# source_eagle.net
KiCad netlist of a schematic drawn in EAGLE
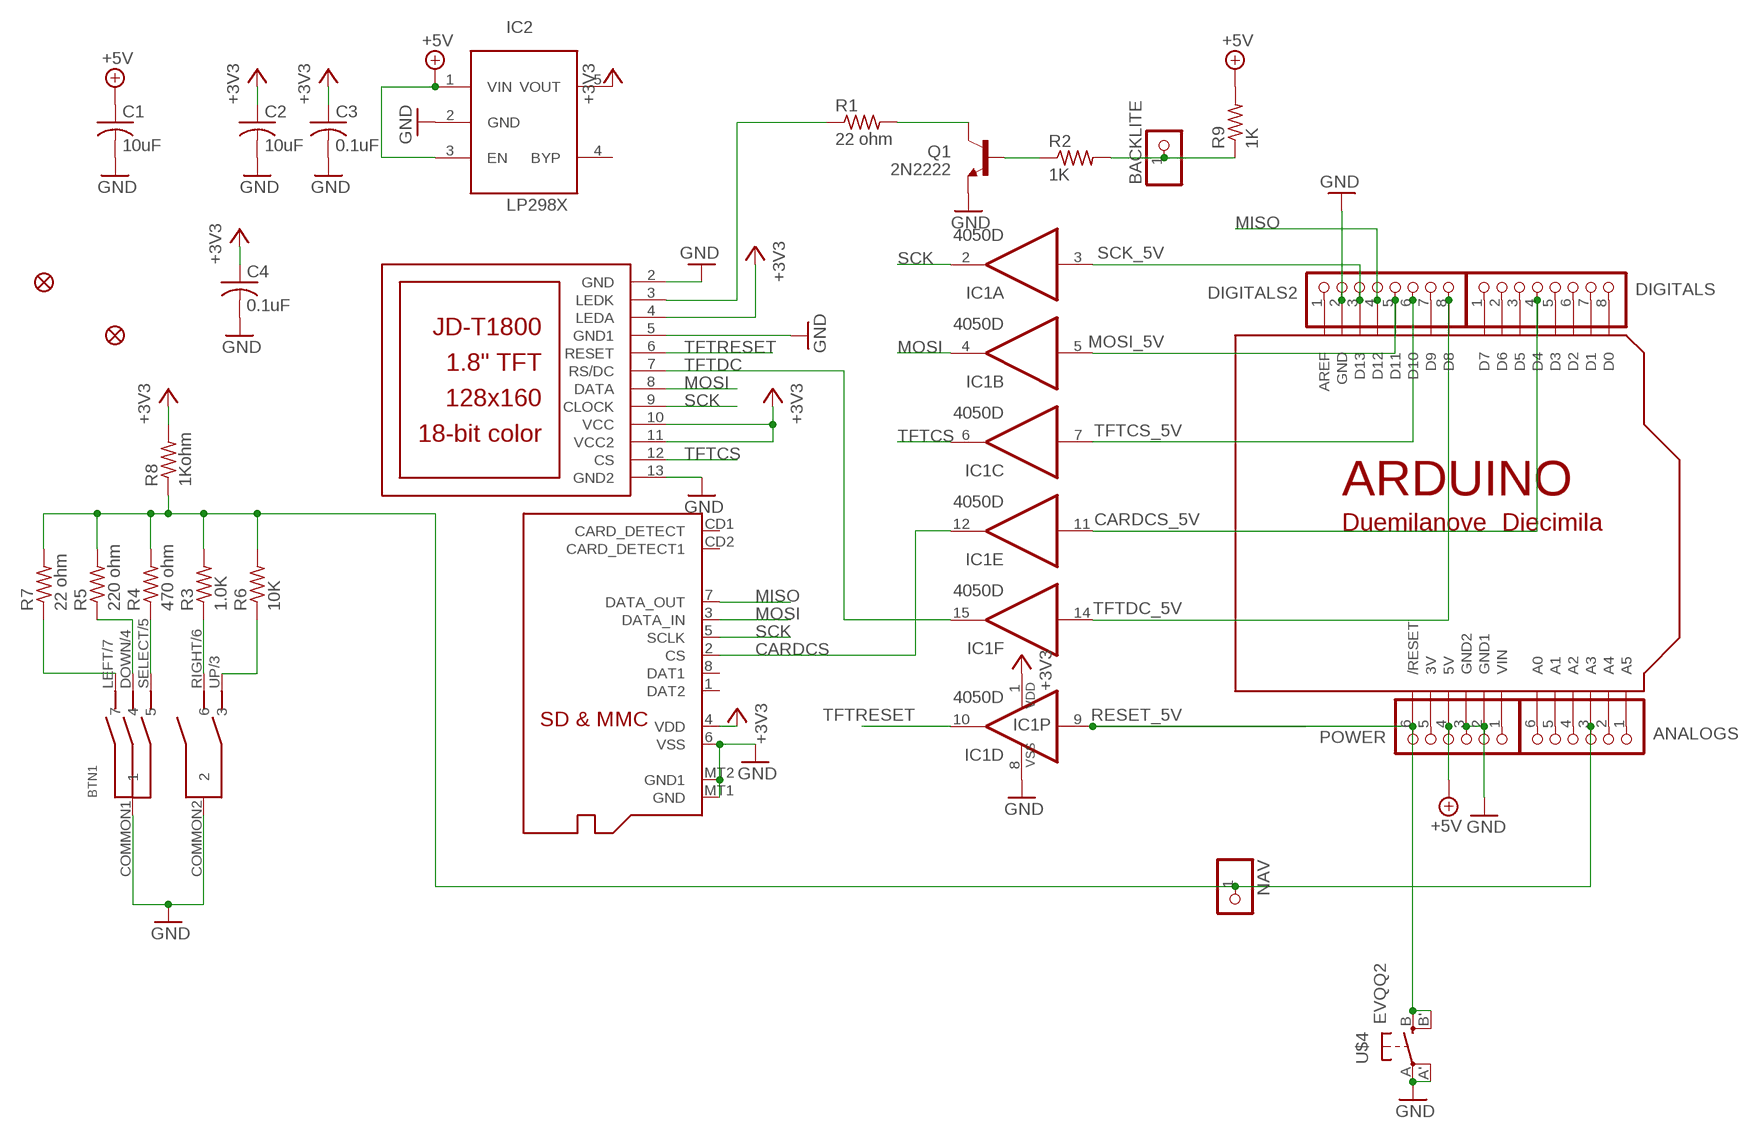
[diagram p0: schematic, sheet 1]

(export (version "E")
  (design (tool "Eeschema 10.0.6"))
  (components
    (comp (ref "ANALOGS")
      (value "PINHD-1X6CB")
      (footprint "eagle-import:1X06-CLEANBIG")
      (libsource (lib "eagle-import") (part "PINHD-1X6CB"))
    )
    (comp (ref "BACKLITE")
      (value "PINHD-1X1")
      (footprint "eagle-import:1X01")
      (libsource (lib "eagle-import") (part "PINHD-1X1"))
    )
    (comp (ref "BTN1")
      (value "SWITCH_4WAY_TPA511GLFS")
      (footprint "eagle-import:SWITCH_4WAY_TPA511GLFS")
      (libsource (lib "eagle-import") (part "SWITCH_4WAY_TPA511GLFS"))
    )
    (comp (ref "C1")
      (value "10uF")
      (footprint "eagle-import:C0805K")
      (libsource (lib "eagle-import") (part "C-USC0805K"))
    )
    (comp (ref "C2")
      (value "10uF")
      (footprint "eagle-import:C0805K")
      (libsource (lib "eagle-import") (part "C-USC0805K"))
    )
    (comp (ref "C3")
      (value "0.1uF")
      (footprint "eagle-import:C0805K")
      (libsource (lib "eagle-import") (part "C-USC0805K"))
    )
    (comp (ref "C4")
      (value "0.1uF")
      (footprint "eagle-import:C0805K")
      (libsource (lib "eagle-import") (part "C-USC0805K"))
    )
    (comp (ref "DIGITALS")
      (value "PINHD-1X8CLEANBIG")
      (footprint "eagle-import:1X08-CLEANBIG")
      (libsource (lib "eagle-import") (part "PINHD-1X8CLEANBIG"))
    )
    (comp (ref "DIGITALS2")
      (value "PINHD-1X8CLEANBIG")
      (footprint "eagle-import:1X08-CLEANBIG")
      (libsource (lib "eagle-import") (part "PINHD-1X8CLEANBIG"))
    )
    (comp (ref "FID1")
      (value "FIDUCIAL1X2.5")
      (footprint "eagle-import:FIDUCIAL-1X2.5")
      (libsource (lib "eagle-import") (part "FIDUCIAL1X2.5"))
    )
    (comp (ref "FID3")
      (value "FIDUCIAL1X2.5")
      (footprint "eagle-import:FIDUCIAL-1X2.5")
      (libsource (lib "eagle-import") (part "FIDUCIAL1X2.5"))
    )
    (comp (ref "IC1")
      (value "4050D")
      (footprint "eagle-import:SO16")
      (libsource (lib "eagle-import") (part "4050D"))
    )
    (comp (ref "IC2")
      (value "RT9193-33GB")
      (footprint "eagle-import:SOT23-5L")
      (libsource (lib "eagle-import") (part "LP298XS"))
    )
    (comp (ref "NAV")
      (value "PINHD-1X1")
      (footprint "eagle-import:1X01")
      (libsource (lib "eagle-import") (part "PINHD-1X1"))
    )
    (comp (ref "POWER")
      (value "PINHD-1X6CB")
      (footprint "eagle-import:1X06-CLEANBIG")
      (libsource (lib "eagle-import") (part "PINHD-1X6CB"))
    )
    (comp (ref "Q1")
      (value "2N2222")
      (footprint "eagle-import:SOT23-BEC")
      (libsource (lib "eagle-import") (part "-NPN-SOT23-BECMMBT2222ALT1"))
    )
    (comp (ref "R1")
      (value "22 ohm")
      (footprint "eagle-import:R0805")
      (libsource (lib "eagle-import") (part "R-US_R0805"))
    )
    (comp (ref "R2")
      (value "1K")
      (footprint "eagle-import:R0805")
      (libsource (lib "eagle-import") (part "R-US_R0805"))
    )
    (comp (ref "R3")
      (value "1.0K")
      (footprint "eagle-import:R0805")
      (libsource (lib "eagle-import") (part "R-US_R0805"))
    )
    (comp (ref "R4")
      (value "470 ohm")
      (footprint "eagle-import:R0805")
      (libsource (lib "eagle-import") (part "R-US_R0805"))
    )
    (comp (ref "R5")
      (value "220 ohm")
      (footprint "eagle-import:R0805")
      (libsource (lib "eagle-import") (part "R-US_R0805"))
    )
    (comp (ref "R6")
      (value "10K")
      (footprint "eagle-import:R0805")
      (libsource (lib "eagle-import") (part "R-US_R0805"))
    )
    (comp (ref "R7")
      (value "22 ohm")
      (footprint "eagle-import:R0805")
      (libsource (lib "eagle-import") (part "R-US_R0805"))
    )
    (comp (ref "R8")
      (value "1Kohm")
      (footprint "eagle-import:R0805")
      (libsource (lib "eagle-import") (part "R-US_R0805"))
    )
    (comp (ref "R9")
      (value "1K")
      (footprint "eagle-import:R0805")
      (libsource (lib "eagle-import") (part "R-US_R0805"))
    )
    (comp (ref "U$1")
      (value "JD-T1800")
      (footprint "eagle-import:JD-T1800")
      (libsource (lib "eagle-import") (part "JD-T1800"))
    )
    (comp (ref "U$2")
      (value "ARDUINOUNO")
      (footprint "eagle-import:ARDUINO")
      (libsource (lib "eagle-import") (part "ARDUINOUNO"))
    )
    (comp (ref "U$3")
      (value "MICROSD")
      (footprint "eagle-import:MICROSD")
      (libsource (lib "eagle-import") (part "MICROSD"))
    )
    (comp (ref "U$4")
      (value "EVQQ2")
      (footprint "eagle-import:EVQ-Q2")
      (libsource (lib "eagle-import") (part "EVQQ2"))
    )
  )
  (nets
    (net (code "1") (name "+3V3") (class "Default")
      (node (ref "C2") (pin "1") (pinfunction "1_1") (pintype "passive"))
      (node (ref "C3") (pin "1") (pinfunction "1_1") (pintype "passive"))
      (node (ref "C4") (pin "1") (pinfunction "1_1") (pintype "passive"))
      (node (ref "IC1") (pin "1") (pinfunction "VDD_1") (pintype "power_in"))
      (node (ref "IC2") (pin "5") (pinfunction "VOUT_5") (pintype "bidirectional"))
      (node (ref "R8") (pin "2") (pinfunction "2_2") (pintype "passive"))
      (node (ref "U$1") (pin "10") (pinfunction "VCC_10") (pintype "power_in"))
      (node (ref "U$1") (pin "11") (pinfunction "VCC2_11") (pintype "power_in"))
      (node (ref "U$1") (pin "4") (pinfunction "LEDA_4") (pintype "input"))
      (node (ref "U$3") (pin "4") (pinfunction "VDD_4") (pintype "power_in"))
    )
    (net (code "2") (name "+5V") (class "Default")
      (node (ref "C1") (pin "1") (pinfunction "1_1") (pintype "passive"))
      (node (ref "IC2") (pin "1") (pinfunction "VIN_1") (pintype "bidirectional"))
      (node (ref "IC2") (pin "3") (pinfunction "EN_3") (pintype "bidirectional"))
      (node (ref "POWER") (pin "4") (pinfunction "4_4") (pintype "passive"))
      (node (ref "R9") (pin "2") (pinfunction "2_2") (pintype "passive"))
      (node (ref "U$2") (pin "5V") (pinfunction "5V_5V") (pintype "power_in"))
    )
    (net (code "3") (name "/CARDCS") (class "Default")
      (node (ref "IC1") (pin "12") (pinfunction "O_12") (pintype "output"))
      (node (ref "U$3") (pin "2") (pinfunction "CS_2") (pintype "input"))
    )
    (net (code "4") (name "/CARDCS_5V") (class "Default")
      (node (ref "DIGITALS") (pin "4") (pinfunction "4_4") (pintype "passive"))
      (node (ref "IC1") (pin "11") (pinfunction "I_11") (pintype "input"))
      (node (ref "U$2") (pin "D4") (pinfunction "D4_D4") (pintype "bidirectional"))
    )
    (net (code "5") (name "/MISO") (class "Default")
      (node (ref "DIGITALS2") (pin "4") (pinfunction "4_4") (pintype "passive"))
      (node (ref "U$2") (pin "D12") (pinfunction "D12_D12") (pintype "bidirectional"))
      (node (ref "U$3") (pin "7") (pinfunction "DATA_OUT_7") (pintype "output"))
    )
    (net (code "6") (name "/MOSI") (class "Default")
      (node (ref "IC1") (pin "4") (pinfunction "O_4") (pintype "output"))
      (node (ref "U$1") (pin "8") (pinfunction "DATA_8") (pintype "bidirectional"))
      (node (ref "U$3") (pin "3") (pinfunction "DATA_IN_3") (pintype "input"))
    )
    (net (code "7") (name "/MOSI_5V") (class "Default")
      (node (ref "DIGITALS2") (pin "5") (pinfunction "5_5") (pintype "passive"))
      (node (ref "IC1") (pin "5") (pinfunction "I_5") (pintype "input"))
      (node (ref "U$2") (pin "D11") (pinfunction "D11_D11") (pintype "bidirectional"))
    )
    (net (code "8") (name "/RESET_5V") (class "Default")
      (node (ref "IC1") (pin "9") (pinfunction "I_9") (pintype "input"))
      (node (ref "POWER") (pin "6") (pinfunction "6_6") (pintype "passive"))
      (node (ref "U$2") (pin "RESET") (pinfunction "/RESET_RESET") (pintype "bidirectional"))
      (node (ref "U$4") (pin "B") (pinfunction "S_B") (pintype "passive"))
      (node (ref "U$4") (pin "B'") (pinfunction "S1_B'") (pintype "passive"))
    )
    (net (code "9") (name "/SCK") (class "Default")
      (node (ref "IC1") (pin "2") (pinfunction "O_2") (pintype "output"))
      (node (ref "U$1") (pin "9") (pinfunction "CLOCK_9") (pintype "input"))
      (node (ref "U$3") (pin "5") (pinfunction "SCLK_5") (pintype "input"))
    )
    (net (code "10") (name "/SCK_5V") (class "Default")
      (node (ref "DIGITALS2") (pin "3") (pinfunction "3_3") (pintype "passive"))
      (node (ref "IC1") (pin "3") (pinfunction "I_3") (pintype "input"))
      (node (ref "U$2") (pin "D13") (pinfunction "D13_D13") (pintype "bidirectional"))
    )
    (net (code "11") (name "/TFTCS") (class "Default")
      (node (ref "IC1") (pin "6") (pinfunction "O_6") (pintype "output"))
      (node (ref "U$1") (pin "12") (pinfunction "CS_12") (pintype "input"))
    )
    (net (code "12") (name "/TFTCS_5V") (class "Default")
      (node (ref "DIGITALS2") (pin "6") (pinfunction "6_6") (pintype "passive"))
      (node (ref "IC1") (pin "7") (pinfunction "I_7") (pintype "input"))
      (node (ref "U$2") (pin "D10") (pinfunction "D10_D10") (pintype "bidirectional"))
    )
    (net (code "13") (name "/TFTDC") (class "Default")
      (node (ref "IC1") (pin "15") (pinfunction "O_15") (pintype "output"))
      (node (ref "U$1") (pin "7") (pinfunction "RS/DC_7") (pintype "input"))
    )
    (net (code "14") (name "/TFTDC_5V") (class "Default")
      (node (ref "DIGITALS2") (pin "8") (pinfunction "8_8") (pintype "passive"))
      (node (ref "IC1") (pin "14") (pinfunction "I_14") (pintype "input"))
      (node (ref "U$2") (pin "D8") (pinfunction "D8_D8") (pintype "bidirectional"))
    )
    (net (code "15") (name "/TFTRESET") (class "Default")
      (node (ref "IC1") (pin "10") (pinfunction "O_10") (pintype "output"))
      (node (ref "U$1") (pin "6") (pinfunction "RESET_6") (pintype "input"))
    )
    (net (code "16") (name "GND") (class "Default")
      (node (ref "BTN1") (pin "COMMON1") (pinfunction "1_COMMON1") (pintype "bidirectional"))
      (node (ref "BTN1") (pin "COMMON2") (pinfunction "2_COMMON2") (pintype "bidirectional"))
      (node (ref "C1") (pin "2") (pinfunction "2_2") (pintype "passive"))
      (node (ref "C2") (pin "2") (pinfunction "2_2") (pintype "passive"))
      (node (ref "C3") (pin "2") (pinfunction "2_2") (pintype "passive"))
      (node (ref "C4") (pin "2") (pinfunction "2_2") (pintype "passive"))
      (node (ref "DIGITALS2") (pin "2") (pinfunction "2_2") (pintype "passive"))
      (node (ref "IC1") (pin "8") (pinfunction "VSS_8") (pintype "power_in"))
      (node (ref "IC2") (pin "2") (pinfunction "GND_2") (pintype "bidirectional"))
      (node (ref "POWER") (pin "2") (pinfunction "2_2") (pintype "passive"))
      (node (ref "POWER") (pin "3") (pinfunction "3_3") (pintype "passive"))
      (node (ref "Q1") (pin "E") (pinfunction "E_E") (pintype "passive"))
      (node (ref "U$1") (pin "13") (pinfunction "GND2_13") (pintype "power_in"))
      (node (ref "U$1") (pin "2") (pinfunction "GND_2") (pintype "power_in"))
      (node (ref "U$1") (pin "5") (pinfunction "GND1_5") (pintype "power_in"))
      (node (ref "U$2") (pin "GND") (pinfunction "GND_GND") (pintype "power_in"))
      (node (ref "U$2") (pin "GND1") (pinfunction "GND1_GND1") (pintype "power_in"))
      (node (ref "U$2") (pin "GND2") (pinfunction "GND2_GND2") (pintype "power_in"))
      (node (ref "U$3") (pin "6") (pinfunction "VSS_6") (pintype "power_in"))
      (node (ref "U$3") (pin "MT1") (pinfunction "GND_MT1") (pintype "power_in"))
      (node (ref "U$3") (pin "MT2") (pinfunction "GND1_MT2") (pintype "power_in"))
      (node (ref "U$4") (pin "A") (pinfunction "P_A") (pintype "passive"))
      (node (ref "U$4") (pin "A'") (pinfunction "P1_A'") (pintype "passive"))
    )
    (net (code "17") (name "Net-(ANALOGS-Pad1)") (class "Default")
      (node (ref "ANALOGS") (pin "1") (pinfunction "1_1") (pintype "passive"))
      (node (ref "U$2") (pin "A5") (pinfunction "A5_A5") (pintype "bidirectional"))
    )
    (net (code "18") (name "Net-(ANALOGS-Pad2)") (class "Default")
      (node (ref "ANALOGS") (pin "2") (pinfunction "2_2") (pintype "passive"))
      (node (ref "U$2") (pin "A4") (pinfunction "A4_A4") (pintype "bidirectional"))
    )
    (net (code "19") (name "Net-(ANALOGS-Pad3)") (class "Default")
      (node (ref "ANALOGS") (pin "3") (pinfunction "3_3") (pintype "passive"))
      (node (ref "NAV") (pin "1") (pinfunction "1_1") (pintype "passive"))
      (node (ref "R3") (pin "2") (pinfunction "2_2") (pintype "passive"))
      (node (ref "R4") (pin "2") (pinfunction "2_2") (pintype "passive"))
      (node (ref "R5") (pin "2") (pinfunction "2_2") (pintype "passive"))
      (node (ref "R6") (pin "2") (pinfunction "2_2") (pintype "passive"))
      (node (ref "R7") (pin "2") (pinfunction "2_2") (pintype "passive"))
      (node (ref "R8") (pin "1") (pinfunction "1_1") (pintype "passive"))
      (node (ref "U$2") (pin "A3") (pinfunction "A3_A3") (pintype "bidirectional"))
    )
    (net (code "20") (name "Net-(ANALOGS-Pad4)") (class "Default")
      (node (ref "ANALOGS") (pin "4") (pinfunction "4_4") (pintype "passive"))
      (node (ref "U$2") (pin "A2") (pinfunction "A2_A2") (pintype "bidirectional"))
    )
    (net (code "21") (name "Net-(ANALOGS-Pad5)") (class "Default")
      (node (ref "ANALOGS") (pin "5") (pinfunction "5_5") (pintype "passive"))
      (node (ref "U$2") (pin "A1") (pinfunction "A1_A1") (pintype "bidirectional"))
    )
    (net (code "22") (name "Net-(ANALOGS-Pad6)") (class "Default")
      (node (ref "ANALOGS") (pin "6") (pinfunction "6_6") (pintype "passive"))
      (node (ref "U$2") (pin "A0") (pinfunction "A0_A0") (pintype "bidirectional"))
    )
    (net (code "23") (name "Net-(BACKLITE-Pad1)") (class "Default")
      (node (ref "BACKLITE") (pin "1") (pinfunction "1_1") (pintype "passive"))
      (node (ref "R2") (pin "2") (pinfunction "2_2") (pintype "passive"))
      (node (ref "R9") (pin "1") (pinfunction "1_1") (pintype "passive"))
    )
    (net (code "24") (name "Net-(BTN1-3)") (class "Default")
      (node (ref "BTN1") (pin "UP/3") (pinfunction "3_UP/3") (pintype "bidirectional"))
      (node (ref "R6") (pin "1") (pinfunction "1_1") (pintype "passive"))
    )
    (net (code "25") (name "Net-(BTN1-4)") (class "Default")
      (node (ref "BTN1") (pin "DOWN/4") (pinfunction "4_DOWN/4") (pintype "bidirectional"))
      (node (ref "R5") (pin "1") (pinfunction "1_1") (pintype "passive"))
    )
    (net (code "26") (name "Net-(BTN1-5)") (class "Default")
      (node (ref "BTN1") (pin "SELECT/5") (pinfunction "5_SELECT/5") (pintype "bidirectional"))
      (node (ref "R4") (pin "1") (pinfunction "1_1") (pintype "passive"))
    )
    (net (code "27") (name "Net-(BTN1-6)") (class "Default")
      (node (ref "BTN1") (pin "RIGHT/6") (pinfunction "6_RIGHT/6") (pintype "bidirectional"))
      (node (ref "R3") (pin "1") (pinfunction "1_1") (pintype "passive"))
    )
    (net (code "28") (name "Net-(BTN1-7)") (class "Default")
      (node (ref "BTN1") (pin "LEFT/7") (pinfunction "7_LEFT/7") (pintype "bidirectional"))
      (node (ref "R7") (pin "1") (pinfunction "1_1") (pintype "passive"))
    )
    (net (code "29") (name "Net-(DIGITALS-Pad1)") (class "Default")
      (node (ref "DIGITALS") (pin "1") (pinfunction "1_1") (pintype "passive"))
      (node (ref "U$2") (pin "D7") (pinfunction "D7_D7") (pintype "bidirectional"))
    )
    (net (code "30") (name "Net-(DIGITALS-Pad2)") (class "Default")
      (node (ref "DIGITALS") (pin "2") (pinfunction "2_2") (pintype "passive"))
      (node (ref "U$2") (pin "D6") (pinfunction "D6_D6") (pintype "bidirectional"))
    )
    (net (code "31") (name "Net-(DIGITALS-Pad3)") (class "Default")
      (node (ref "DIGITALS") (pin "3") (pinfunction "3_3") (pintype "passive"))
      (node (ref "U$2") (pin "D5") (pinfunction "D5_D5") (pintype "bidirectional"))
    )
    (net (code "32") (name "Net-(DIGITALS-Pad5)") (class "Default")
      (node (ref "DIGITALS") (pin "5") (pinfunction "5_5") (pintype "passive"))
      (node (ref "U$2") (pin "D3") (pinfunction "D3_D3") (pintype "bidirectional"))
    )
    (net (code "33") (name "Net-(DIGITALS-Pad6)") (class "Default")
      (node (ref "DIGITALS") (pin "6") (pinfunction "6_6") (pintype "passive"))
      (node (ref "U$2") (pin "D2") (pinfunction "D2_D2") (pintype "bidirectional"))
    )
    (net (code "34") (name "Net-(DIGITALS-Pad7)") (class "Default")
      (node (ref "DIGITALS") (pin "7") (pinfunction "7_7") (pintype "passive"))
      (node (ref "U$2") (pin "D1") (pinfunction "D1_D1") (pintype "bidirectional"))
    )
    (net (code "35") (name "Net-(DIGITALS-Pad8)") (class "Default")
      (node (ref "DIGITALS") (pin "8") (pinfunction "8_8") (pintype "passive"))
      (node (ref "U$2") (pin "D0") (pinfunction "D0_D0") (pintype "bidirectional"))
    )
    (net (code "36") (name "Net-(DIGITALS2-Pad1)") (class "Default")
      (node (ref "DIGITALS2") (pin "1") (pinfunction "1_1") (pintype "passive"))
      (node (ref "U$2") (pin "AREF") (pinfunction "AREF_AREF") (pintype "bidirectional"))
    )
    (net (code "37") (name "Net-(DIGITALS2-Pad7)") (class "Default")
      (node (ref "DIGITALS2") (pin "7") (pinfunction "7_7") (pintype "passive"))
      (node (ref "U$2") (pin "D9") (pinfunction "D9_D9") (pintype "bidirectional"))
    )
    (net (code "38") (name "Net-(POWER-Pad1)") (class "Default")
      (node (ref "POWER") (pin "1") (pinfunction "1_1") (pintype "passive"))
      (node (ref "U$2") (pin "VIN") (pinfunction "VIN_VIN") (pintype "power_in"))
    )
    (net (code "39") (name "Net-(POWER-Pad5)") (class "Default")
      (node (ref "POWER") (pin "5") (pinfunction "5_5") (pintype "passive"))
      (node (ref "U$2") (pin "3V") (pinfunction "3V_3V") (pintype "power_in"))
    )
    (net (code "40") (name "Net-(Q1-PadB)") (class "Default")
      (node (ref "Q1") (pin "B") (pinfunction "B_B") (pintype "passive"))
      (node (ref "R2") (pin "1") (pinfunction "1_1") (pintype "passive"))
    )
    (net (code "41") (name "Net-(Q1-PadC)") (class "Default")
      (node (ref "Q1") (pin "C") (pinfunction "C_C") (pintype "passive"))
      (node (ref "R1") (pin "2") (pinfunction "2_2") (pintype "passive"))
    )
    (net (code "42") (name "Net-(U$1-LEDK)") (class "Default")
      (node (ref "R1") (pin "1") (pinfunction "1_1") (pintype "passive"))
      (node (ref "U$1") (pin "3") (pinfunction "LEDK_3") (pintype "input"))
    )
    (net (code "43") (name "unconnected-(IC2-BYP-Pad4)") (class "Default")
      (node (ref "IC2") (pin "4") (pinfunction "BYP_4") (pintype "bidirectional"))
    )
    (net (code "44") (name "unconnected-(U$3-CARD_DETECT-PadCD1)") (class "Default")
      (node (ref "U$3") (pin "CD1") (pinfunction "CARD_DETECT_CD1") (pintype "passive"))
    )
    (net (code "45") (name "unconnected-(U$3-CARD_DETECT1-PadCD2)") (class "Default")
      (node (ref "U$3") (pin "CD2") (pinfunction "CARD_DETECT1_CD2") (pintype "passive"))
    )
    (net (code "46") (name "unconnected-(U$3-DAT1-Pad8)") (class "Default")
      (node (ref "U$3") (pin "8") (pinfunction "DAT1_8") (pintype "bidirectional"))
    )
    (net (code "47") (name "unconnected-(U$3-DAT2-Pad1)") (class "Default")
      (node (ref "U$3") (pin "1") (pinfunction "DAT2_1") (pintype "bidirectional"))
    )
  )
)
